# voltage5vto3_3_MIC5205.net
KiCad netlist of a schematic drawn in EAGLE
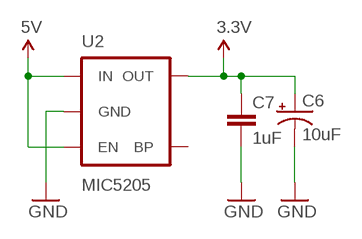
[diagram p0: schematic, sheet 1]

(export (version "E")
  (design (tool "Eeschema 10.0.6"))
  (components
    (comp (ref "C6")
      (value "10uF")
      (footprint "eagle-import:EIA3216")
      (libsource (lib "eagle-import") (part "CAP_POL1206"))
    )
    (comp (ref "C7")
      (value "1uF")
      (footprint "eagle-import:0603-CAP")
      (libsource (lib "eagle-import") (part "CAP0603-CAP"))
    )
    (comp (ref "U2")
      (value "MIC5205")
      (footprint "eagle-import:SOT23-5")
      (libsource (lib "eagle-import") (part "V_REG_LDOSMD"))
    )
  )
  (nets
    (net (code "1") (name "3.3V") (class "Default")
      (node (ref "C6") (pin "A") (pinfunction "+_A") (pintype "passive"))
      (node (ref "C7") (pin "1") (pinfunction "1_1") (pintype "passive"))
      (node (ref "U2") (pin "5") (pinfunction "OUT_5") (pintype "passive"))
    )
    (net (code "2") (name "5V") (class "Default")
      (node (ref "U2") (pin "1") (pinfunction "IN_1") (pintype "input"))
      (node (ref "U2") (pin "3") (pinfunction "EN_3") (pintype "input"))
    )
    (net (code "3") (name "GND") (class "Default")
      (node (ref "C6") (pin "C") (pinfunction "-_C") (pintype "passive"))
      (node (ref "C7") (pin "2") (pinfunction "2_2") (pintype "passive"))
      (node (ref "U2") (pin "2") (pinfunction "GND_2") (pintype "input"))
    )
    (net (code "4") (name "unconnected-(U2-BP-Pad4)") (class "Default")
      (node (ref "U2") (pin "4") (pinfunction "BP_4") (pintype "input"))
    )
  )
)
